# mainboard.net
KiCad netlist of a schematic drawn in EAGLE
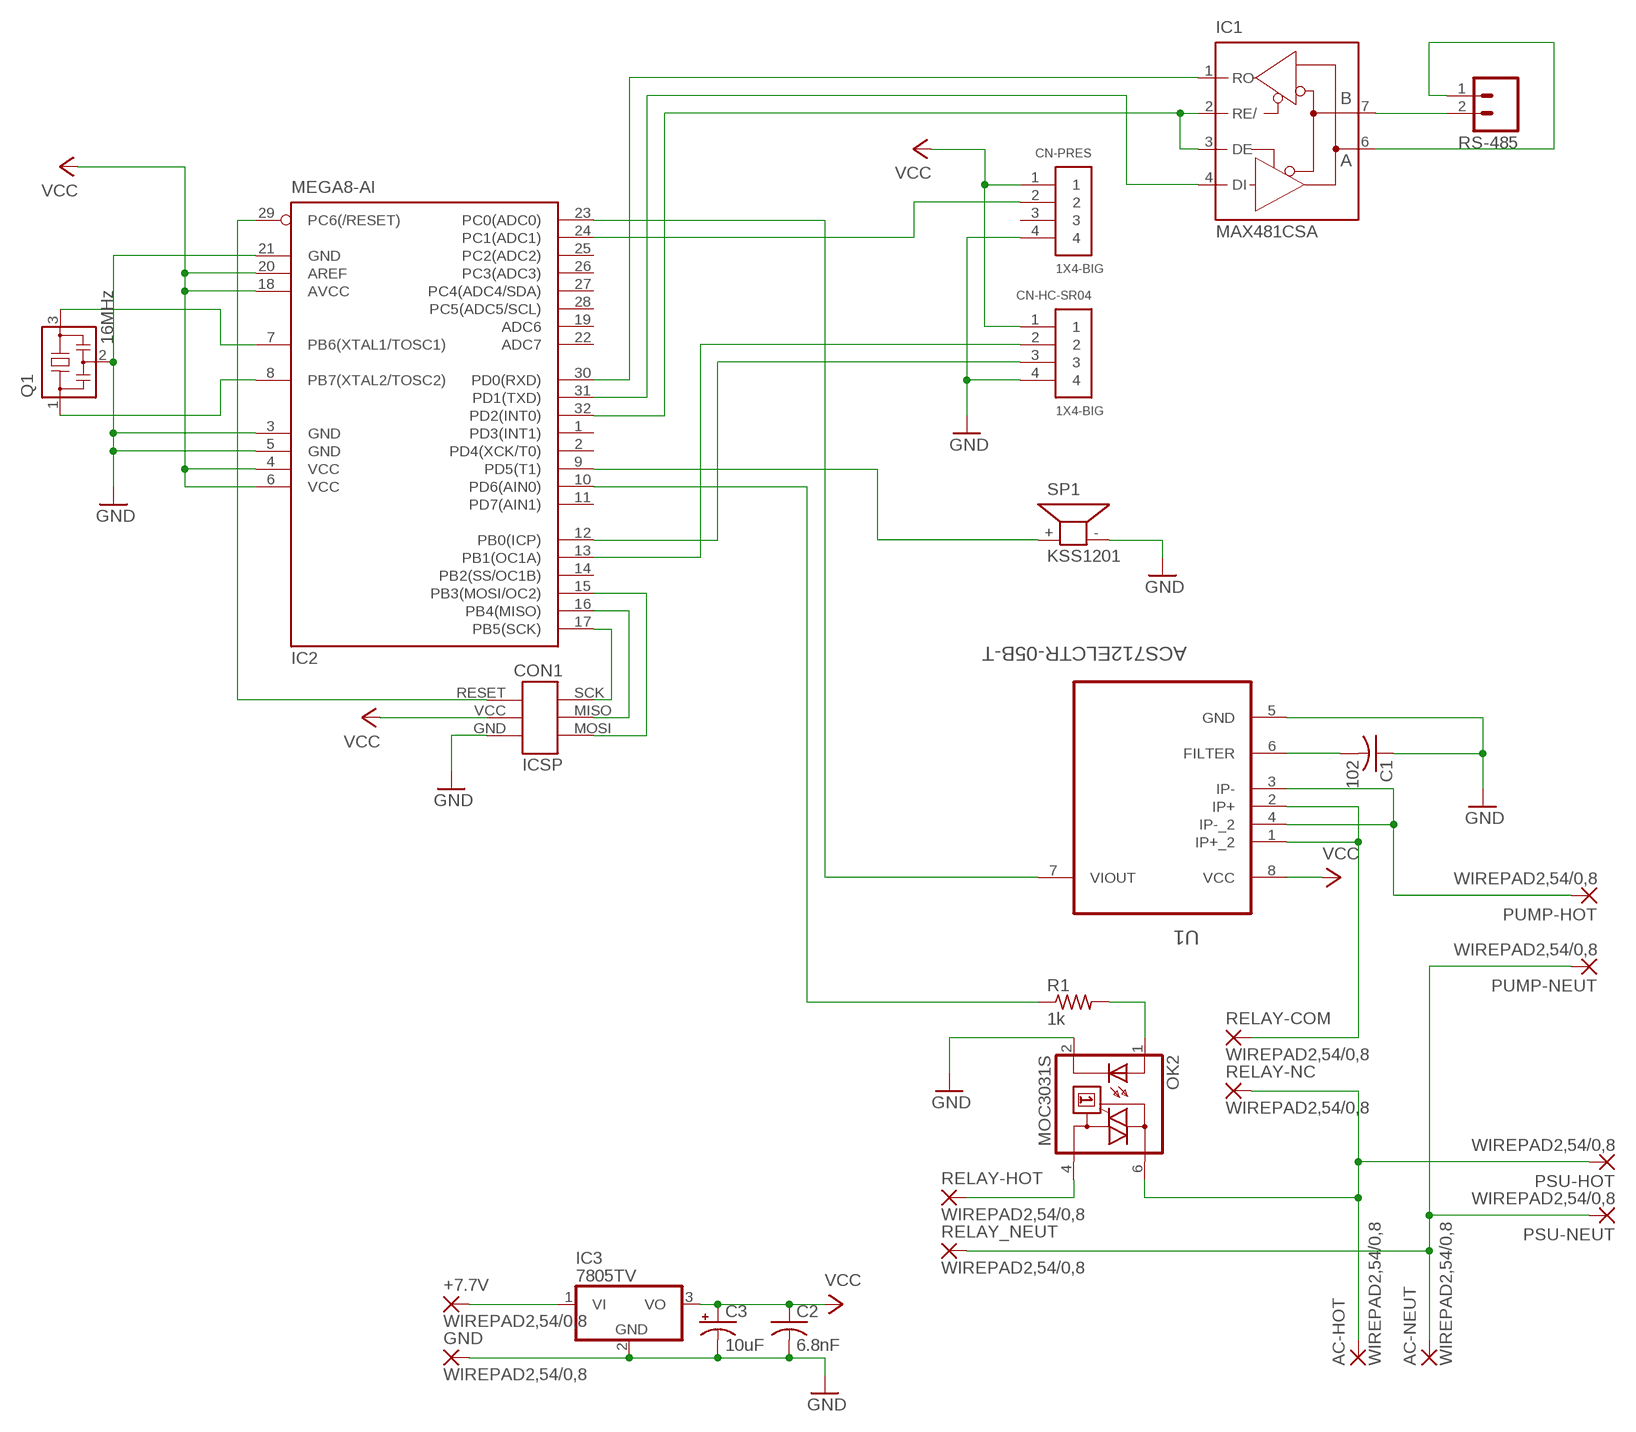
[diagram p0: schematic, sheet 1]

(export (version "E")
  (design (tool "Eeschema 10.0.6"))
  (components
    (comp (ref "+7.7V")
      (value "WIREPAD2,54/0,8")
      (footprint "eagle-import:2,54_0,8")
      (libsource (lib "eagle-import") (part "WIREPAD2,54/0,8"))
    )
    (comp (ref "AC-HOT")
      (value "WIREPAD2,54/0,8")
      (footprint "eagle-import:2,54_0,8")
      (libsource (lib "eagle-import") (part "WIREPAD2,54/0,8"))
    )
    (comp (ref "AC-NEUT")
      (value "WIREPAD2,54/0,8")
      (footprint "eagle-import:2,54_0,8")
      (libsource (lib "eagle-import") (part "WIREPAD2,54/0,8"))
    )
    (comp (ref "C1")
      (value "102")
      (footprint "eagle-import:C025-024X044")
      (libsource (lib "eagle-import") (part "C-US025-024X044"))
    )
    (comp (ref "C2")
      (value "6.8nF")
      (footprint "eagle-import:C050-024X044")
      (libsource (lib "eagle-import") (part "C-US050-024X044"))
    )
    (comp (ref "C3")
      (value "10uF")
      (footprint "eagle-import:E1,8-4")
      (libsource (lib "eagle-import") (part "CPOL-USE1.8-4"))
    )
    (comp (ref "CN-HC-SR04")
      (value "1X4-BIG")
      (footprint "eagle-import:1X04-BIG")
      (libsource (lib "eagle-import") (part "1X4-BIG"))
    )
    (comp (ref "CN-PRES")
      (value "1X4-BIG")
      (footprint "eagle-import:1X04-BIG")
      (libsource (lib "eagle-import") (part "1X4-BIG"))
    )
    (comp (ref "CON1")
      (value "ICSP-HEADER")
      (footprint "eagle-import:ICSP-HEADER")
      (libsource (lib "eagle-import") (part "ICSP-HEADER"))
    )
    (comp (ref "GND")
      (value "WIREPAD2,54/0,8")
      (footprint "eagle-import:2,54_0,8")
      (libsource (lib "eagle-import") (part "WIREPAD2,54/0,8"))
    )
    (comp (ref "IC1")
      (value "MAX481CSA")
      (footprint "eagle-import:SO08")
      (fields (field (name "MF") "MAXIM"))
      (libsource (lib "eagle-import") (part "MAX481CSA"))
    )
    (comp (ref "IC2")
      (value "MEGA8-AI")
      (footprint "eagle-import:TQFP32-08")
      (fields (field (name "MPN") "ATMEGA8-16AU"))
      (libsource (lib "eagle-import") (part "MEGA8-AI"))
    )
    (comp (ref "IC3")
      (value "7805TV")
      (footprint "eagle-import:TO220V")
      (libsource (lib "eagle-import") (part "78TV05"))
    )
    (comp (ref "OK2")
      (value "MOC3031S")
      (footprint "eagle-import:DIL6-SMD")
      (fields (field (name "MF") "FAIRCHILD SEMICONDUCTOR") (field (name "MPN") "MOC3031SM"))
      (libsource (lib "eagle-import") (part "MOC30S31"))
    )
    (comp (ref "PSU-HOT")
      (value "WIREPAD2,54/0,8")
      (footprint "eagle-import:2,54_0,8")
      (libsource (lib "eagle-import") (part "WIREPAD2,54/0,8"))
    )
    (comp (ref "PSU-NEUT")
      (value "WIREPAD2,54/0,8")
      (footprint "eagle-import:2,54_0,8")
      (libsource (lib "eagle-import") (part "WIREPAD2,54/0,8"))
    )
    (comp (ref "PUMP-HOT")
      (value "WIREPAD2,54/0,8")
      (footprint "eagle-import:2,54_0,8")
      (libsource (lib "eagle-import") (part "WIREPAD2,54/0,8"))
    )
    (comp (ref "PUMP-NEUT")
      (value "WIREPAD2,54/0,8")
      (footprint "eagle-import:2,54_0,8")
      (libsource (lib "eagle-import") (part "WIREPAD2,54/0,8"))
    )
    (comp (ref "Q1")
      (value "16MHz")
      (footprint "eagle-import:RESONATOR")
      (libsource (lib "eagle-import") (part "RESONATOR"))
    )
    (comp (ref "R1")
      (value "1k")
      (footprint "eagle-import:R0603")
      (libsource (lib "eagle-import") (part "R-US_R0603"))
    )
    (comp (ref "RELAY-COM")
      (value "WIREPAD2,54/0,8")
      (footprint "eagle-import:2,54_0,8")
      (libsource (lib "eagle-import") (part "WIREPAD2,54/0,8"))
    )
    (comp (ref "RELAY-HOT")
      (value "WIREPAD2,54/0,8")
      (footprint "eagle-import:2,54_0,8")
      (libsource (lib "eagle-import") (part "WIREPAD2,54/0,8"))
    )
    (comp (ref "RELAY-NC")
      (value "WIREPAD2,54/0,8")
      (footprint "eagle-import:2,54_0,8")
      (libsource (lib "eagle-import") (part "WIREPAD2,54/0,8"))
    )
    (comp (ref "RELAY_NEUT")
      (value "WIREPAD2,54/0,8")
      (footprint "eagle-import:2,54_0,8")
      (libsource (lib "eagle-import") (part "WIREPAD2,54/0,8"))
    )
    (comp (ref "RS-485")
      (value "M02")
      (footprint "eagle-import:02P")
      (libsource (lib "eagle-import") (part "M02"))
    )
    (comp (ref "SP1")
      (value "KSS1201")
      (footprint "eagle-import:KSS1201")
      (libsource (lib "eagle-import") (part "KSS1201"))
    )
    (comp (ref "U1")
      (value "ACS712ELCTR-05B-T")
      (footprint "eagle-import:SOIC127P600X175-8N")
      (libsource (lib "eagle-import") (part "ACS712ELCTR-05B-T"))
    )
  )
  (nets
    (net (code "1") (name "GND") (class "Default")
      (node (ref "C1") (pin "1") (pinfunction "1_1") (pintype "passive"))
      (node (ref "C2") (pin "2") (pinfunction "2_2") (pintype "passive"))
      (node (ref "C3") (pin "-") (pinfunction "-_-") (pintype "passive"))
      (node (ref "CN-HC-SR04") (pin "4") (pinfunction "4_4") (pintype "bidirectional"))
      (node (ref "CN-PRES") (pin "4") (pinfunction "4_4") (pintype "bidirectional"))
      (node (ref "CON1") (pin "GND") (pinfunction "GND_GND") (pintype "bidirectional"))
      (node (ref "GND") (pin "1") (pinfunction "P_1") (pintype "passive"))
      (node (ref "IC2") (pin "21") (pinfunction "GND_21") (pintype "power_in"))
      (node (ref "IC2") (pin "3") (pinfunction "GND_3") (pintype "power_in"))
      (node (ref "IC2") (pin "5") (pinfunction "GND_5") (pintype "power_in"))
      (node (ref "IC3") (pin "2") (pinfunction "GND_2") (pintype "passive"))
      (node (ref "OK2") (pin "2") (pinfunction "C_2") (pintype "passive"))
      (node (ref "Q1") (pin "2") (pinfunction "2_2") (pintype "passive"))
      (node (ref "SP1") (pin "-") (pinfunction "2_-") (pintype "passive"))
      (node (ref "U1") (pin "5") (pinfunction "GND_5") (pintype "passive"))
    )
    (net (code "2") (name "Net-(+7.7V-P)") (class "Default")
      (node (ref "+7.7V") (pin "1") (pinfunction "P_1") (pintype "passive"))
      (node (ref "IC3") (pin "1") (pinfunction "VI_1") (pintype "input"))
    )
    (net (code "3") (name "Net-(AC-HOT-P)") (class "Default")
      (node (ref "AC-HOT") (pin "1") (pinfunction "P_1") (pintype "passive"))
      (node (ref "OK2") (pin "6") (pinfunction "A2_6") (pintype "passive"))
      (node (ref "PSU-HOT") (pin "1") (pinfunction "P_1") (pintype "passive"))
      (node (ref "RELAY-NC") (pin "1") (pinfunction "P_1") (pintype "passive"))
    )
    (net (code "4") (name "Net-(AC-NEUT-P)") (class "Default")
      (node (ref "AC-NEUT") (pin "1") (pinfunction "P_1") (pintype "passive"))
      (node (ref "PSU-NEUT") (pin "1") (pinfunction "P_1") (pintype "passive"))
      (node (ref "PUMP-NEUT") (pin "1") (pinfunction "P_1") (pintype "passive"))
      (node (ref "RELAY_NEUT") (pin "1") (pinfunction "P_1") (pintype "passive"))
    )
    (net (code "5") (name "Net-(IC1A-A)") (class "Default")
      (node (ref "IC1") (pin "6") (pinfunction "A_6") (pintype "passive"))
      (node (ref "RS-485") (pin "1") (pinfunction "1_1") (pintype "passive"))
    )
    (net (code "6") (name "Net-(IC1A-B)") (class "Default")
      (node (ref "IC1") (pin "7") (pinfunction "B_7") (pintype "passive"))
      (node (ref "RS-485") (pin "2") (pinfunction "2_2") (pintype "passive"))
    )
    (net (code "7") (name "Net-(IC1A-DE)") (class "Default")
      (node (ref "IC1") (pin "2") (pinfunction "RE/_2") (pintype "input"))
      (node (ref "IC1") (pin "3") (pinfunction "DE_3") (pintype "input"))
      (node (ref "IC2") (pin "32") (pinfunction "PD2(INT0)_32") (pintype "bidirectional"))
    )
    (net (code "8") (name "Net-(IC1A-DI)") (class "Default")
      (node (ref "IC1") (pin "4") (pinfunction "DI_4") (pintype "input"))
      (node (ref "IC2") (pin "31") (pinfunction "PD1(TXD)_31") (pintype "bidirectional"))
    )
    (net (code "9") (name "Net-(IC1A-RO)") (class "Default")
      (node (ref "IC1") (pin "1") (pinfunction "RO_1") (pintype "output"))
      (node (ref "IC2") (pin "30") (pinfunction "PD0(RXD)_30") (pintype "bidirectional"))
    )
    (net (code "10") (name "Net-(IC2-PB0(ICP))") (class "Default")
      (node (ref "CN-HC-SR04") (pin "3") (pinfunction "3_3") (pintype "bidirectional"))
      (node (ref "IC2") (pin "12") (pinfunction "PB0(ICP)_12") (pintype "bidirectional"))
    )
    (net (code "11") (name "Net-(IC2-PB1(OC1A))") (class "Default")
      (node (ref "CN-HC-SR04") (pin "2") (pinfunction "2_2") (pintype "bidirectional"))
      (node (ref "IC2") (pin "13") (pinfunction "PB1(OC1A)_13") (pintype "bidirectional"))
    )
    (net (code "12") (name "Net-(IC2-PB3(MOSI{slash}OC2))") (class "Default")
      (node (ref "CON1") (pin "MOSI") (pinfunction "MOSI_MOSI") (pintype "bidirectional"))
      (node (ref "IC2") (pin "15") (pinfunction "PB3(MOSI/OC2)_15") (pintype "bidirectional"))
    )
    (net (code "13") (name "Net-(IC2-PB4(MISO))") (class "Default")
      (node (ref "CON1") (pin "MISO") (pinfunction "MISO_MISO") (pintype "bidirectional"))
      (node (ref "IC2") (pin "16") (pinfunction "PB4(MISO)_16") (pintype "bidirectional"))
    )
    (net (code "14") (name "Net-(IC2-PB5(SCK))") (class "Default")
      (node (ref "CON1") (pin "SCK") (pinfunction "SCK_SCK") (pintype "bidirectional"))
      (node (ref "IC2") (pin "17") (pinfunction "PB5(SCK)_17") (pintype "bidirectional"))
    )
    (net (code "15") (name "Net-(IC2-PB6(XTAL1{slash}TOSC1))") (class "Default")
      (node (ref "IC2") (pin "7") (pinfunction "PB6(XTAL1/TOSC1)_7") (pintype "bidirectional"))
      (node (ref "Q1") (pin "3") (pinfunction "3_3") (pintype "passive"))
    )
    (net (code "16") (name "Net-(IC2-PB7(XTAL2{slash}TOSC2))") (class "Default")
      (node (ref "IC2") (pin "8") (pinfunction "PB7(XTAL2/TOSC2)_8") (pintype "bidirectional"))
      (node (ref "Q1") (pin "1") (pinfunction "1_1") (pintype "passive"))
    )
    (net (code "17") (name "Net-(IC2-PC0(ADC0))") (class "Default")
      (node (ref "IC2") (pin "23") (pinfunction "PC0(ADC0)_23") (pintype "bidirectional"))
      (node (ref "U1") (pin "7") (pinfunction "VIOUT_7") (pintype "output"))
    )
    (net (code "18") (name "Net-(IC2-PC1(ADC1))") (class "Default")
      (node (ref "CN-PRES") (pin "2") (pinfunction "2_2") (pintype "bidirectional"))
      (node (ref "IC2") (pin "24") (pinfunction "PC1(ADC1)_24") (pintype "bidirectional"))
    )
    (net (code "19") (name "Net-(IC2-PC6({slash}RESET))") (class "Default")
      (node (ref "CON1") (pin "RESET") (pinfunction "RESET_RESET") (pintype "bidirectional"))
      (node (ref "IC2") (pin "29") (pinfunction "PC6(/RESET)_29") (pintype "bidirectional"))
    )
    (net (code "20") (name "Net-(IC2-PD5(T1))") (class "Default")
      (node (ref "IC2") (pin "9") (pinfunction "PD5(T1)_9") (pintype "bidirectional"))
      (node (ref "SP1") (pin "+") (pinfunction "1_+") (pintype "passive"))
    )
    (net (code "21") (name "Net-(IC2-PD6(AIN0))") (class "Default")
      (node (ref "IC2") (pin "10") (pinfunction "PD6(AIN0)_10") (pintype "bidirectional"))
      (node (ref "R1") (pin "1") (pinfunction "1_1") (pintype "passive"))
    )
    (net (code "22") (name "Net-(OK2-A)") (class "Default")
      (node (ref "OK2") (pin "1") (pinfunction "A_1") (pintype "passive"))
      (node (ref "R1") (pin "2") (pinfunction "2_2") (pintype "passive"))
    )
    (net (code "23") (name "Net-(OK2-A1)") (class "Default")
      (node (ref "OK2") (pin "4") (pinfunction "A1_4") (pintype "passive"))
      (node (ref "RELAY-HOT") (pin "1") (pinfunction "P_1") (pintype "passive"))
    )
    (net (code "24") (name "Net-(PUMP-HOT-P)") (class "Default")
      (node (ref "PUMP-HOT") (pin "1") (pinfunction "P_1") (pintype "passive"))
      (node (ref "U1") (pin "3") (pinfunction "IP-_3") (pintype "input"))
      (node (ref "U1") (pin "4") (pinfunction "IP-_2_4") (pintype "input"))
    )
    (net (code "25") (name "Net-(RELAY-COM-P)") (class "Default")
      (node (ref "RELAY-COM") (pin "1") (pinfunction "P_1") (pintype "passive"))
      (node (ref "U1") (pin "1") (pinfunction "IP+_2_1") (pintype "input"))
      (node (ref "U1") (pin "2") (pinfunction "IP+_2") (pintype "input"))
    )
    (net (code "26") (name "Net-(U1-FILTER)") (class "Default")
      (node (ref "C1") (pin "2") (pinfunction "2_2") (pintype "passive"))
      (node (ref "U1") (pin "6") (pinfunction "FILTER_6") (pintype "input"))
    )
    (net (code "27") (name "VCC") (class "Default")
      (node (ref "C2") (pin "1") (pinfunction "1_1") (pintype "passive"))
      (node (ref "C3") (pin "+") (pinfunction "+_+") (pintype "passive"))
      (node (ref "CN-HC-SR04") (pin "1") (pinfunction "1_1") (pintype "bidirectional"))
      (node (ref "CN-PRES") (pin "1") (pinfunction "1_1") (pintype "bidirectional"))
      (node (ref "CON1") (pin "VCC") (pinfunction "+5V_VCC") (pintype "bidirectional"))
      (node (ref "IC2") (pin "18") (pinfunction "AVCC_18") (pintype "power_in"))
      (node (ref "IC2") (pin "20") (pinfunction "AREF_20") (pintype "passive"))
      (node (ref "IC2") (pin "4") (pinfunction "VCC_4") (pintype "power_in"))
      (node (ref "IC2") (pin "6") (pinfunction "VCC_6") (pintype "power_in"))
      (node (ref "IC3") (pin "3") (pinfunction "VO_3") (pintype "passive"))
      (node (ref "U1") (pin "8") (pinfunction "VCC_8") (pintype "power_in"))
    )
    (net (code "28") (name "unconnected-(CN-PRES-Pad3)") (class "Default")
      (node (ref "CN-PRES") (pin "3") (pinfunction "3_3") (pintype "bidirectional"))
    )
    (net (code "29") (name "unconnected-(IC2-ADC6-Pad19)") (class "Default")
      (node (ref "IC2") (pin "19") (pinfunction "ADC6_19") (pintype "bidirectional"))
    )
    (net (code "30") (name "unconnected-(IC2-ADC7-Pad22)") (class "Default")
      (node (ref "IC2") (pin "22") (pinfunction "ADC7_22") (pintype "bidirectional"))
    )
    (net (code "31") (name "unconnected-(IC2-PB2(SS{slash}OC1B)-Pad14)") (class "Default")
      (node (ref "IC2") (pin "14") (pinfunction "PB2(SS/OC1B)_14") (pintype "bidirectional"))
    )
    (net (code "32") (name "unconnected-(IC2-PC2(ADC2)-Pad25)") (class "Default")
      (node (ref "IC2") (pin "25") (pinfunction "PC2(ADC2)_25") (pintype "bidirectional"))
    )
    (net (code "33") (name "unconnected-(IC2-PC3(ADC3)-Pad26)") (class "Default")
      (node (ref "IC2") (pin "26") (pinfunction "PC3(ADC3)_26") (pintype "bidirectional"))
    )
    (net (code "34") (name "unconnected-(IC2-PC4(ADC4{slash}SDA)-Pad27)") (class "Default")
      (node (ref "IC2") (pin "27") (pinfunction "PC4(ADC4/SDA)_27") (pintype "bidirectional"))
    )
    (net (code "35") (name "unconnected-(IC2-PC5(ADC5{slash}SCL)-Pad28)") (class "Default")
      (node (ref "IC2") (pin "28") (pinfunction "PC5(ADC5/SCL)_28") (pintype "bidirectional"))
    )
    (net (code "36") (name "unconnected-(IC2-PD3(INT1)-Pad1)") (class "Default")
      (node (ref "IC2") (pin "1") (pinfunction "PD3(INT1)_1") (pintype "bidirectional"))
    )
    (net (code "37") (name "unconnected-(IC2-PD4(XCK{slash}T0)-Pad2)") (class "Default")
      (node (ref "IC2") (pin "2") (pinfunction "PD4(XCK/T0)_2") (pintype "bidirectional"))
    )
    (net (code "38") (name "unconnected-(IC2-PD7(AIN1)-Pad11)") (class "Default")
      (node (ref "IC2") (pin "11") (pinfunction "PD7(AIN1)_11") (pintype "bidirectional"))
    )
  )
)
